# prototype1.net
KiCad netlist of a schematic drawn in EAGLE
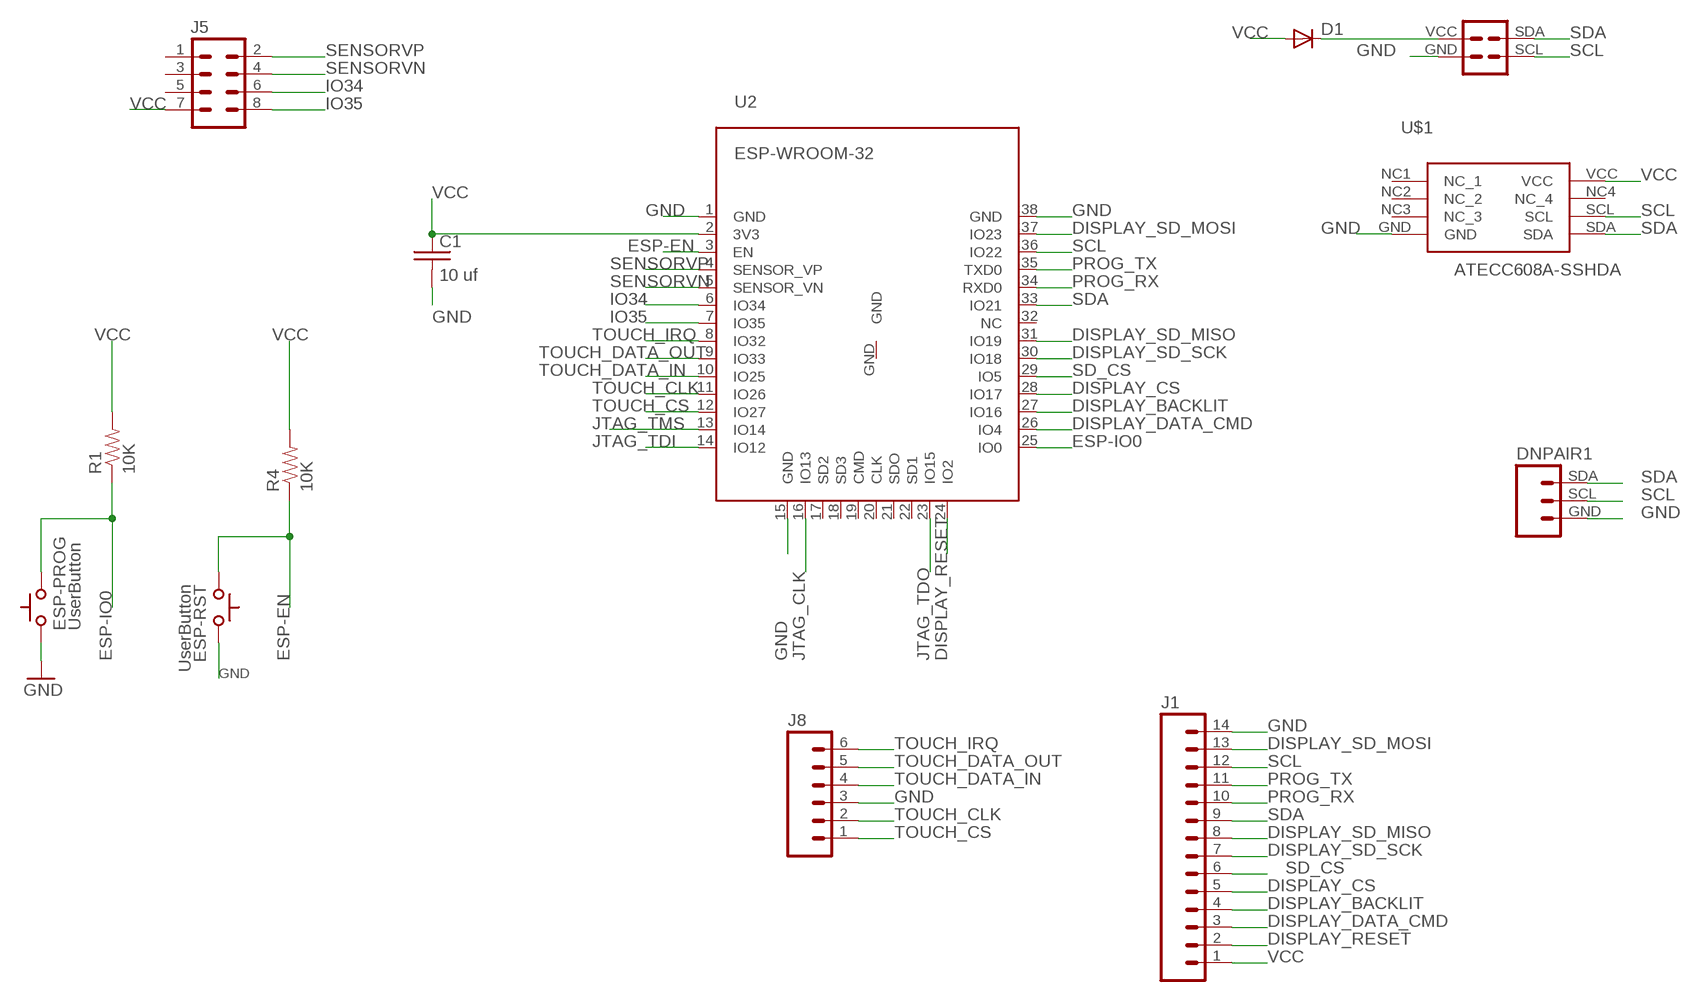
[diagram p0: schematic, sheet 1]
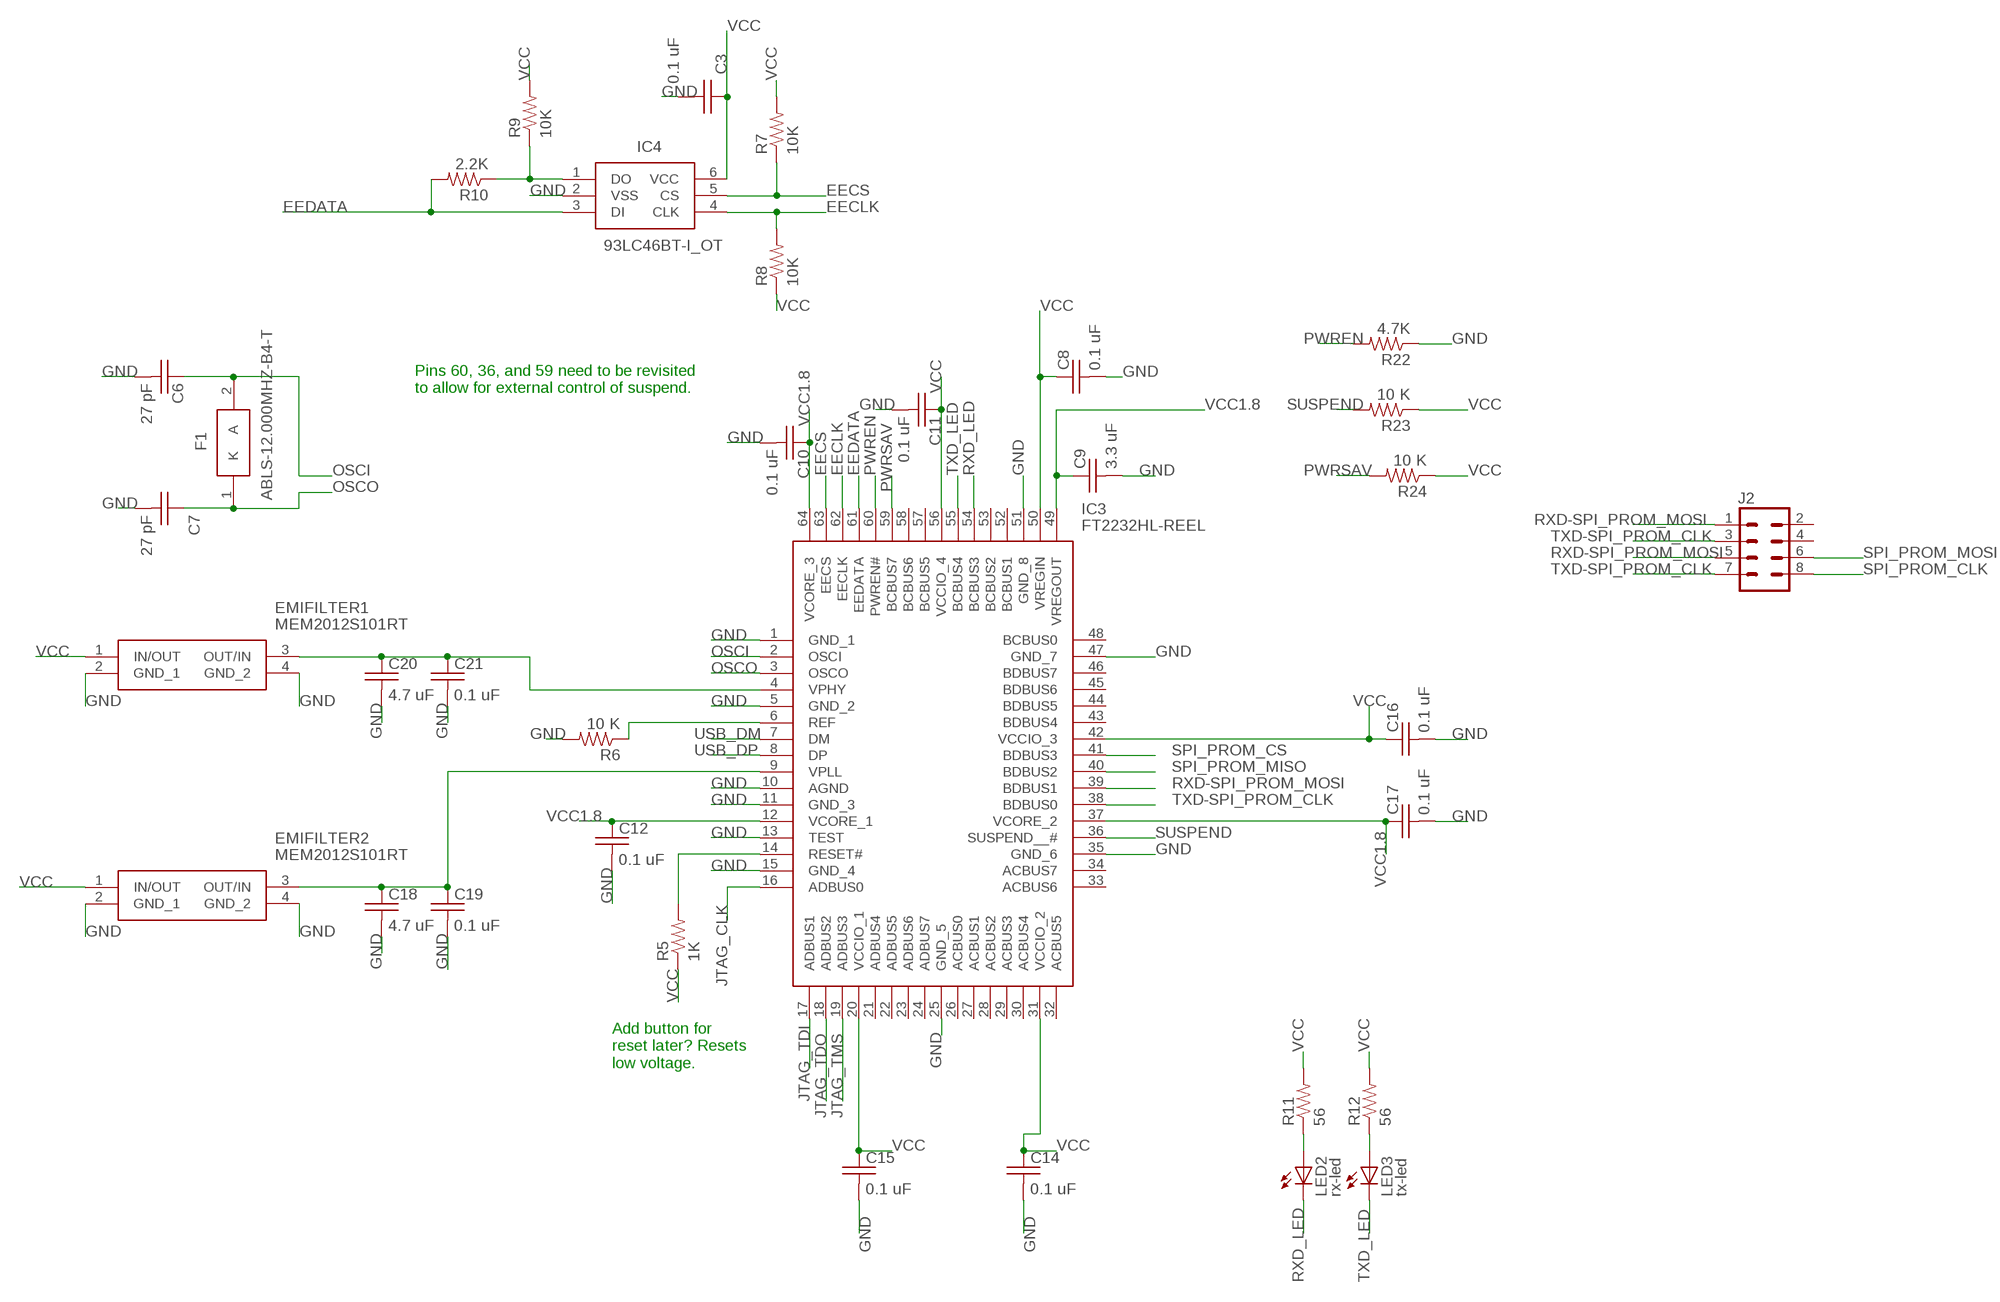
[diagram p1: schematic, sheet 2]
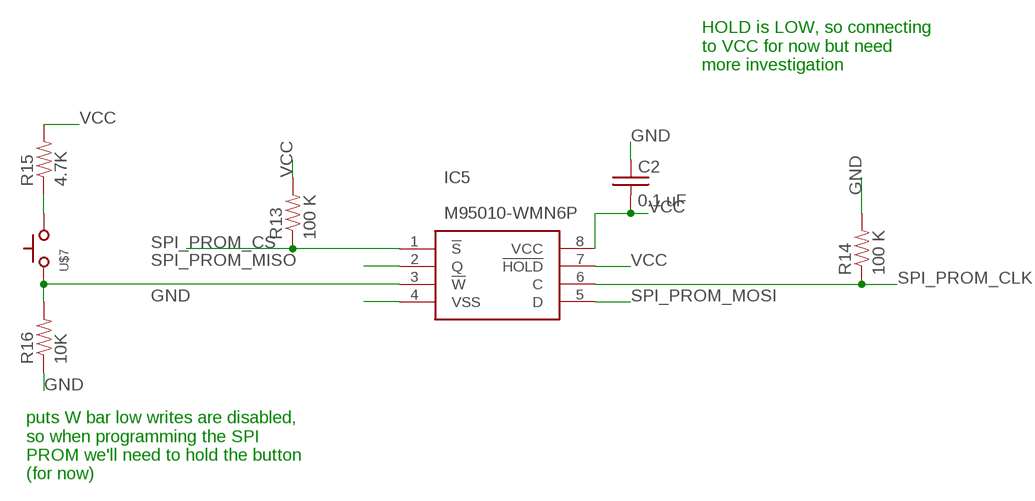
[diagram p2: schematic, sheet 3]
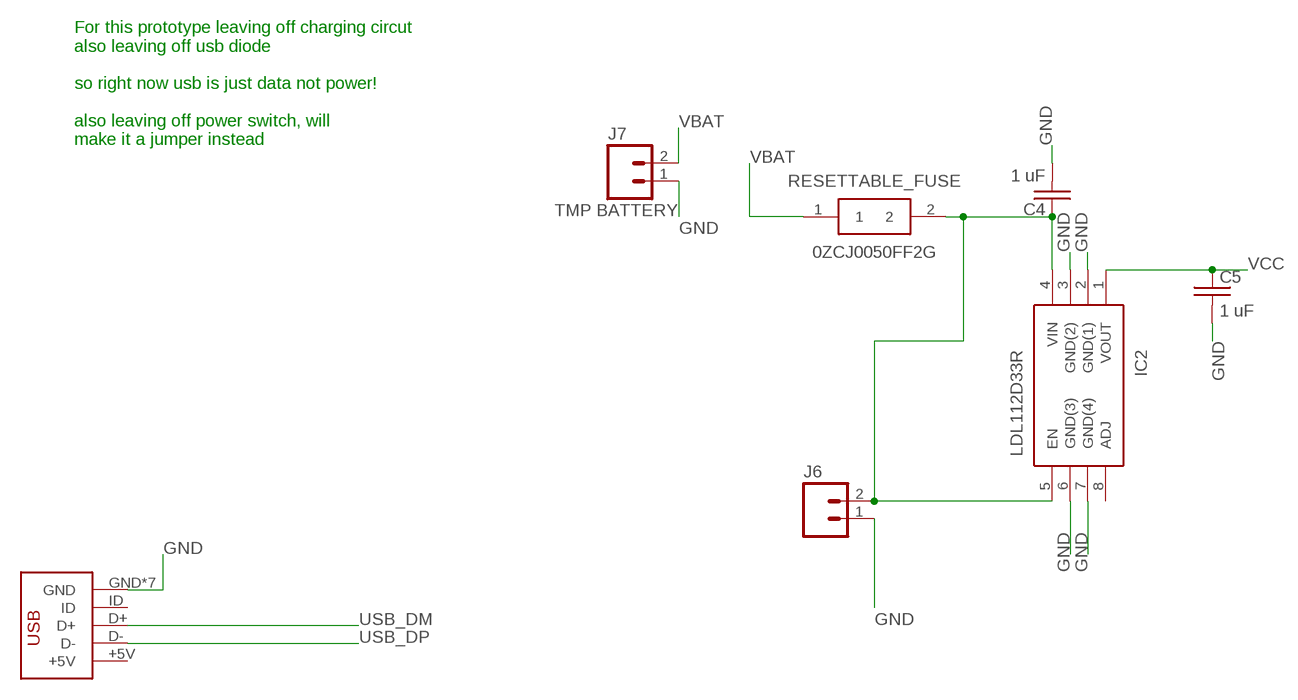
[diagram p3: schematic, sheet 4]
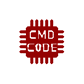
[diagram p4: schematic, sheet 5]

(export (version "E")
  (design (tool "Eeschema 10.0.6"))
  (components
    (comp (ref "C3")
      (value "0.1 uF")
      (footprint "eagle-import:C0805")
      (libsource (lib "eagle-import") (part "C-USC0805"))
    )
    (comp (ref "C6")
      (value "27 pF")
      (footprint "eagle-import:C0805")
      (libsource (lib "eagle-import") (part "C-USC0805"))
    )
    (comp (ref "C7")
      (value "27 pF")
      (footprint "eagle-import:C0805")
      (libsource (lib "eagle-import") (part "C-USC0805"))
    )
    (comp (ref "C8")
      (value "0.1 uF")
      (footprint "eagle-import:C0805")
      (libsource (lib "eagle-import") (part "C-USC0805"))
    )
    (comp (ref "C9")
      (value "3.3 uF")
      (footprint "eagle-import:C0805")
      (libsource (lib "eagle-import") (part "C-USC0805"))
    )
    (comp (ref "C10")
      (value "0.1 uF")
      (footprint "eagle-import:C0805")
      (libsource (lib "eagle-import") (part "C-USC0805"))
    )
    (comp (ref "C11")
      (value "0.1 uF")
      (footprint "eagle-import:C0805")
      (libsource (lib "eagle-import") (part "C-USC0805"))
    )
    (comp (ref "C12")
      (value "0.1 uF")
      (footprint "eagle-import:C0805")
      (libsource (lib "eagle-import") (part "C-USC0805"))
    )
    (comp (ref "C14")
      (value "0.1 uF")
      (footprint "eagle-import:C0805")
      (libsource (lib "eagle-import") (part "C-USC0805"))
    )
    (comp (ref "C15")
      (value "0.1 uF")
      (footprint "eagle-import:C0805")
      (libsource (lib "eagle-import") (part "C-USC0805"))
    )
    (comp (ref "C16")
      (value "0.1 uF")
      (footprint "eagle-import:C0805")
      (libsource (lib "eagle-import") (part "C-USC0805"))
    )
    (comp (ref "C17")
      (value "0.1 uF")
      (footprint "eagle-import:C0805")
      (libsource (lib "eagle-import") (part "C-USC0805"))
    )
    (comp (ref "C18")
      (value "4.7 uF")
      (footprint "eagle-import:C0805")
      (libsource (lib "eagle-import") (part "C-USC0805"))
    )
    (comp (ref "C19")
      (value "0.1 uF")
      (footprint "eagle-import:C0805")
      (libsource (lib "eagle-import") (part "C-USC0805"))
    )
    (comp (ref "C20")
      (value "4.7 uF")
      (footprint "eagle-import:C0805")
      (libsource (lib "eagle-import") (part "C-USC0805"))
    )
    (comp (ref "C21")
      (value "0.1 uF")
      (footprint "eagle-import:C0805")
      (libsource (lib "eagle-import") (part "C-USC0805"))
    )
    (comp (ref "EMIFILTER1")
      (value "MEM2012S101RT")
      (footprint "eagle-import:MEM2012S101RT")
      (libsource (lib "eagle-import") (part "MEM2012S101RT"))
    )
    (comp (ref "EMIFILTER2")
      (value "MEM2012S101RT")
      (footprint "eagle-import:MEM2012S101RT")
      (libsource (lib "eagle-import") (part "MEM2012S101RT"))
    )
    (comp (ref "F1")
      (value "ABLS-12.000MHZ-B4-T")
      (footprint "eagle-import:HC_49US-(AT49)_1")
      (fields
        (field (name "MOUSER_PART_NUMBER") "815-ABLS-12.0M-T")
        (field (name "RS_PART_NUMBER") "1710207")
      )
      (libsource (lib "eagle-import") (part "ABLS-12.000MHZ-B4-T"))
    )
    (comp (ref "IC3")
      (value "FT2232HL-REEL")
      (footprint "eagle-import:QFP50P1200X1200X160-64N")
      (fields (field (name "MOUSER_PART_NUMBER") "895-FT2232HL"))
      (libsource (lib "eagle-import") (part "FT2232HL-REEL"))
    )
    (comp (ref "IC4")
      (value "93LC46BT-I_OT")
      (footprint "eagle-import:SOT95P270X145-6N")
      (fields
        (field (name "MANUFACTURER_PART_NUMBER") "93LC46BT-I/OT")
        (field (name "MOUSER_PART_NUMBER") "579-93LC46BT-I/OT")
      )
      (libsource (lib "eagle-import") (part "93LC46BT-I_OT"))
    )
    (comp (ref "J2")
      (value "M04X2")
      (footprint "eagle-import:2X4")
      (libsource (lib "eagle-import") (part "M04X2"))
    )
    (comp (ref "LED2")
      (value "rx-led")
      (footprint "eagle-import:LED3MM")
      (libsource (lib "eagle-import") (part "LED3MM"))
    )
    (comp (ref "LED3")
      (value "tx-led")
      (footprint "eagle-import:LED3MM")
      (libsource (lib "eagle-import") (part "LED3MM"))
    )
    (comp (ref "R5")
      (value "1K")
      (footprint "eagle-import:0805")
      (libsource (lib "eagle-import") (part "passives_RESISTOR0805-RES"))
    )
    (comp (ref "R6")
      (value "10 K")
      (footprint "eagle-import:0805")
      (libsource (lib "eagle-import") (part "passives_RESISTOR0805-RES"))
    )
    (comp (ref "R7")
      (value "10K")
      (footprint "eagle-import:0805")
      (libsource (lib "eagle-import") (part "passives_RESISTOR0805-RES"))
    )
    (comp (ref "R8")
      (value "10K")
      (footprint "eagle-import:0805")
      (libsource (lib "eagle-import") (part "passives_RESISTOR0805-RES"))
    )
    (comp (ref "R9")
      (value "10K")
      (footprint "eagle-import:0805")
      (libsource (lib "eagle-import") (part "passives_RESISTOR0805-RES"))
    )
    (comp (ref "R10")
      (value "2.2K")
      (footprint "eagle-import:0805")
      (libsource (lib "eagle-import") (part "passives_RESISTOR0805-RES"))
    )
    (comp (ref "R11")
      (value "56")
      (footprint "eagle-import:0805")
      (libsource (lib "eagle-import") (part "passives_RESISTOR0805-RES"))
    )
    (comp (ref "R12")
      (value "56")
      (footprint "eagle-import:0805")
      (libsource (lib "eagle-import") (part "passives_RESISTOR0805-RES"))
    )
    (comp (ref "R22")
      (value "4.7K")
      (footprint "eagle-import:0805")
      (libsource (lib "eagle-import") (part "passives_RESISTOR0805-RES"))
    )
    (comp (ref "R23")
      (value "10 K")
      (footprint "eagle-import:0805")
      (libsource (lib "eagle-import") (part "passives_RESISTOR0805-RES"))
    )
    (comp (ref "R24")
      (value "10 K")
      (footprint "eagle-import:0805")
      (libsource (lib "eagle-import") (part "passives_RESISTOR0805-RES"))
    )
    (comp (ref "U$3")
      (value "CMD_C0DE_LOGOCMD_CODE_LOGO_TOP_COPPER")
      (footprint "eagle-import:CMD_C0DE_LOGO_TOP_COPPER")
      (libsource (lib "eagle-import") (part "CMD_C0DE_LOGOCMD_CODE_LOGO_TOP_COPPER"))
    )
    (comp (ref "C4")
      (value "1 uF")
      (footprint "eagle-import:C0805")
      (libsource (lib "eagle-import") (part "C-USC0805"))
    )
    (comp (ref "C5")
      (value "1 uF")
      (footprint "eagle-import:C0805")
      (libsource (lib "eagle-import") (part "C-USC0805"))
    )
    (comp (ref "IC2")
      (value "LDL112D33R")
      (footprint "eagle-import:SOIC127P600X175-8N")
      (libsource (lib "eagle-import") (part "LDL112D33R"))
    )
    (comp (ref "J6")
      (value "M02PTH")
      (footprint "eagle-import:1X02")
      (libsource (lib "eagle-import") (part "M02PTH"))
    )
    (comp (ref "J7")
      (value "TMP BATTERY")
      (footprint "eagle-import:1X02")
      (libsource (lib "eagle-import") (part "M02PTH"))
    )
    (comp (ref "RESETTABLE_FUSE")
      (value "0ZCJ0050FF2G")
      (footprint "eagle-import:FUSC3216X55N")
      (libsource (lib "eagle-import") (part "0ZCJ0050FF2G"))
    )
    (comp (ref "U$2")
      (value "DX4R005JJ2DX4R005JJ2")
      (footprint "eagle-import:DX4R005JJ2")
      (libsource (lib "eagle-import") (part "DX4R005JJ2DX4R005JJ2"))
    )
    (comp (ref "C2")
      (value "0.1 uF")
      (footprint "eagle-import:C0805")
      (libsource (lib "eagle-import") (part "C-USC0805"))
    )
    (comp (ref "IC5")
      (value "M95010-WMN6P")
      (footprint "eagle-import:SOIC127P600X175-8N")
      (fields
        (field (name "MOUSER_PART_NUMBER") "511-M95010-WMN6P")
        (field (name "RS_PART_NUMBER") "7147617")
      )
      (libsource (lib "eagle-import") (part "M95010-WMN6P"))
    )
    (comp (ref "R13")
      (value "100 K")
      (footprint "eagle-import:0805")
      (libsource (lib "eagle-import") (part "passives_RESISTOR0805-RES"))
    )
    (comp (ref "R14")
      (value "100 K")
      (footprint "eagle-import:0805")
      (libsource (lib "eagle-import") (part "passives_RESISTOR0805-RES"))
    )
    (comp (ref "R15")
      (value "4.7K")
      (footprint "eagle-import:0805")
      (libsource (lib "eagle-import") (part "passives_RESISTOR0805-RES"))
    )
    (comp (ref "R16")
      (value "10K")
      (footprint "eagle-import:0805")
      (libsource (lib "eagle-import") (part "passives_RESISTOR0805-RES"))
    )
    (comp (ref "U$7")
      (value "SWITCH_TACTILETACTILE-2PIN-NARROW")
      (footprint "eagle-import:TACTILE-2PIN-NARROW")
      (libsource (lib "eagle-import") (part "switches_SWITCH_TACTILETACTILE-2PIN-NARROW"))
    )
    (comp (ref "C1")
      (value "10 uf")
      (footprint "eagle-import:C0805")
      (libsource (lib "eagle-import") (part "C-USC0805"))
    )
    (comp (ref "D1")
      (value "DIODESMA")
      (footprint "eagle-import:SMA-DIODE")
      (libsource (lib "eagle-import") (part "DIODESMA"))
    )
    (comp (ref "DNPAIR1")
      (value "DARKNET_8_PAIR_CONNECTORPTH")
      (footprint "eagle-import:1X03")
      (libsource (lib "eagle-import") (part "DARKNET_8_PAIR_CONNECTORPTH"))
    )
    (comp (ref "ESP-PROG")
      (value "UserButton")
      (footprint "eagle-import:TACTILE-2PIN-NARROW")
      (libsource (lib "eagle-import") (part "SWITCH_TACTILETACTILE-2PIN-NARROW"))
    )
    (comp (ref "ESP-RST")
      (value "UserButton")
      (footprint "eagle-import:TACTILE-2PIN-NARROW")
      (libsource (lib "eagle-import") (part "SWITCH_TACTILETACTILE-2PIN-NARROW"))
    )
    (comp (ref "J1")
      (value "M14")
      (footprint "eagle-import:1X14")
      (libsource (lib "eagle-import") (part "M14"))
    )
    (comp (ref "J5")
      (value "M04X2")
      (footprint "eagle-import:2X4")
      (libsource (lib "eagle-import") (part "M04X2"))
    )
    (comp (ref "J8")
      (value "M06NO_SILK_YES_STOP")
      (footprint "eagle-import:1X06_NO_SILK_YES_STOP")
      (libsource (lib "eagle-import") (part "M06NO_SILK_YES_STOP"))
    )
    (comp (ref "R1")
      (value "10K")
      (footprint "eagle-import:0805")
      (libsource (lib "eagle-import") (part "RESISTOR0805-RES"))
    )
    (comp (ref "R4")
      (value "10K")
      (footprint "eagle-import:0805")
      (libsource (lib "eagle-import") (part "RESISTOR0805-RES"))
    )
    (comp (ref "SHITTY_ADDON")
      (value "SAO1")
      (footprint "eagle-import:DC26SHITTY_ADDON_CONNECTOR")
      (libsource (lib "eagle-import") (part "DC26_SHITTY_ADDON_CONNECTORPTH"))
    )
    (comp (ref "U$1")
      (value "ATECC608A-SSHDA")
      (footprint "eagle-import:8-SOIC")
      (libsource (lib "eagle-import") (part "ATECC608A-SSHDA"))
    )
    (comp (ref "U2")
      (value "ESP-WROOM-32")
      (footprint "eagle-import:ESP-WROOM-32")
      (libsource (lib "eagle-import") (part "ESP-WROOM-32"))
    )
  )
  (nets
    (net (code "1") (name "DISPLAY_BACKLIT") (class "Default")
      (node (ref "J1") (pin "4") (pinfunction "4_4") (pintype "passive"))
      (node (ref "U2") (pin "27") (pinfunction "IO16_27") (pintype "bidirectional"))
    )
    (net (code "2") (name "DISPLAY_CS") (class "Default")
      (node (ref "J1") (pin "5") (pinfunction "5_5") (pintype "passive"))
      (node (ref "U2") (pin "28") (pinfunction "IO17_28") (pintype "bidirectional"))
    )
    (net (code "3") (name "DISPLAY_DATA_CMD") (class "Default")
      (node (ref "J1") (pin "3") (pinfunction "3_3") (pintype "passive"))
      (node (ref "U2") (pin "26") (pinfunction "IO4_26") (pintype "bidirectional"))
    )
    (net (code "4") (name "DISPLAY_RESET") (class "Default")
      (node (ref "J1") (pin "2") (pinfunction "2_2") (pintype "passive"))
      (node (ref "U2") (pin "24") (pinfunction "IO2_24") (pintype "bidirectional"))
    )
    (net (code "5") (name "DISPLAY_SD_MISO") (class "Default")
      (node (ref "J1") (pin "8") (pinfunction "8_8") (pintype "passive"))
      (node (ref "U2") (pin "31") (pinfunction "IO19_31") (pintype "bidirectional"))
    )
    (net (code "6") (name "DISPLAY_SD_MOSI") (class "Default")
      (node (ref "J1") (pin "13") (pinfunction "13_13") (pintype "passive"))
      (node (ref "U2") (pin "37") (pinfunction "IO23_37") (pintype "bidirectional"))
    )
    (net (code "7") (name "DISPLAY_SD_SCK") (class "Default")
      (node (ref "J1") (pin "7") (pinfunction "7_7") (pintype "passive"))
      (node (ref "U2") (pin "30") (pinfunction "IO18_30") (pintype "bidirectional"))
    )
    (net (code "8") (name "EECLK") (class "Default")
      (node (ref "IC3") (pin "62") (pinfunction "EECLK_62") (pintype "bidirectional"))
      (node (ref "IC4") (pin "4") (pinfunction "CLK_4") (pintype "input"))
      (node (ref "R8") (pin "2") (pinfunction "2_2") (pintype "passive"))
    )
    (net (code "9") (name "EECS") (class "Default")
      (node (ref "IC3") (pin "63") (pinfunction "EECS_63") (pintype "bidirectional"))
      (node (ref "IC4") (pin "5") (pinfunction "CS_5") (pintype "input"))
      (node (ref "R7") (pin "1") (pinfunction "1_1") (pintype "passive"))
    )
    (net (code "10") (name "EEDATA") (class "Default")
      (node (ref "IC3") (pin "61") (pinfunction "EEDATA_61") (pintype "bidirectional"))
      (node (ref "IC4") (pin "3") (pinfunction "DI_3") (pintype "bidirectional"))
      (node (ref "R10") (pin "2") (pinfunction "2_2") (pintype "passive"))
    )
    (net (code "11") (name "ESP-EN") (class "Default")
      (node (ref "ESP-RST") (pin "P$2") (pinfunction "C_P$2") (pintype "passive"))
      (node (ref "R4") (pin "1") (pinfunction "1_1") (pintype "passive"))
      (node (ref "U2") (pin "3") (pinfunction "EN_3") (pintype "bidirectional"))
    )
    (net (code "12") (name "ESP-IO0") (class "Default")
      (node (ref "ESP-PROG") (pin "P$1") (pinfunction "A_P$1") (pintype "passive"))
      (node (ref "R1") (pin "1") (pinfunction "1_1") (pintype "passive"))
      (node (ref "U2") (pin "25") (pinfunction "IO0_25") (pintype "bidirectional"))
    )
    (net (code "13") (name "GND") (class "Default")
      (node (ref "C1") (pin "2") (pinfunction "2_2") (pintype "passive"))
      (node (ref "C10") (pin "2") (pinfunction "2_2") (pintype "passive"))
      (node (ref "C11") (pin "2") (pinfunction "2_2") (pintype "passive"))
      (node (ref "C12") (pin "2") (pinfunction "2_2") (pintype "passive"))
      (node (ref "C14") (pin "2") (pinfunction "2_2") (pintype "passive"))
      (node (ref "C15") (pin "2") (pinfunction "2_2") (pintype "passive"))
      (node (ref "C16") (pin "2") (pinfunction "2_2") (pintype "passive"))
      (node (ref "C17") (pin "2") (pinfunction "2_2") (pintype "passive"))
      (node (ref "C18") (pin "2") (pinfunction "2_2") (pintype "passive"))
      (node (ref "C19") (pin "2") (pinfunction "2_2") (pintype "passive"))
      (node (ref "C2") (pin "1") (pinfunction "1_1") (pintype "passive"))
      (node (ref "C20") (pin "2") (pinfunction "2_2") (pintype "passive"))
      (node (ref "C21") (pin "2") (pinfunction "2_2") (pintype "passive"))
      (node (ref "C3") (pin "2") (pinfunction "2_2") (pintype "passive"))
      (node (ref "C4") (pin "2") (pinfunction "2_2") (pintype "passive"))
      (node (ref "C5") (pin "2") (pinfunction "2_2") (pintype "passive"))
      (node (ref "C6") (pin "2") (pinfunction "2_2") (pintype "passive"))
      (node (ref "C7") (pin "2") (pinfunction "2_2") (pintype "passive"))
      (node (ref "C8") (pin "2") (pinfunction "2_2") (pintype "passive"))
      (node (ref "C9") (pin "2") (pinfunction "2_2") (pintype "passive"))
      (node (ref "DNPAIR1") (pin "GND") (pinfunction "GND_GND") (pintype "power_in"))
      (node (ref "EMIFILTER1") (pin "2") (pinfunction "GND_1_2") (pintype "bidirectional"))
      (node (ref "EMIFILTER1") (pin "4") (pinfunction "GND_2_4") (pintype "bidirectional"))
      (node (ref "EMIFILTER2") (pin "2") (pinfunction "GND_1_2") (pintype "bidirectional"))
      (node (ref "EMIFILTER2") (pin "4") (pinfunction "GND_2_4") (pintype "bidirectional"))
      (node (ref "ESP-PROG") (pin "P$2") (pinfunction "C_P$2") (pintype "passive"))
      (node (ref "ESP-RST") (pin "P$1") (pinfunction "A_P$1") (pintype "passive"))
      (node (ref "IC2") (pin "2") (pinfunction "GND(1)_2") (pintype "bidirectional"))
      (node (ref "IC2") (pin "3") (pinfunction "GND(2)_3") (pintype "bidirectional"))
      (node (ref "IC2") (pin "6") (pinfunction "GND(3)_6") (pintype "bidirectional"))
      (node (ref "IC2") (pin "7") (pinfunction "GND(4)_7") (pintype "bidirectional"))
      (node (ref "IC3") (pin "1") (pinfunction "GND_1_1") (pintype "bidirectional"))
      (node (ref "IC3") (pin "10") (pinfunction "AGND_10") (pintype "bidirectional"))
      (node (ref "IC3") (pin "11") (pinfunction "GND_3_11") (pintype "bidirectional"))
      (node (ref "IC3") (pin "13") (pinfunction "TEST_13") (pintype "bidirectional"))
      (node (ref "IC3") (pin "15") (pinfunction "GND_4_15") (pintype "bidirectional"))
      (node (ref "IC3") (pin "25") (pinfunction "GND_5_25") (pintype "bidirectional"))
      (node (ref "IC3") (pin "35") (pinfunction "GND_6_35") (pintype "bidirectional"))
      (node (ref "IC3") (pin "47") (pinfunction "GND_7_47") (pintype "bidirectional"))
      (node (ref "IC3") (pin "5") (pinfunction "GND_2_5") (pintype "bidirectional"))
      (node (ref "IC3") (pin "51") (pinfunction "GND_8_51") (pintype "bidirectional"))
      (node (ref "IC4") (pin "2") (pinfunction "VSS_2") (pintype "power_in"))
      (node (ref "IC5") (pin "4") (pinfunction "VSS_4") (pintype "power_in"))
      (node (ref "J1") (pin "14") (pinfunction "14_14") (pintype "passive"))
      (node (ref "J6") (pin "1") (pinfunction "1_1") (pintype "passive"))
      (node (ref "J7") (pin "1") (pinfunction "1_1") (pintype "passive"))
      (node (ref "J8") (pin "3") (pinfunction "3_3") (pintype "passive"))
      (node (ref "R14") (pin "2") (pinfunction "2_2") (pintype "passive"))
      (node (ref "R16") (pin "1") (pinfunction "1_1") (pintype "passive"))
      (node (ref "R22") (pin "1") (pinfunction "1_1") (pintype "passive"))
      (node (ref "R6") (pin "2") (pinfunction "2_2") (pintype "passive"))
      (node (ref "SHITTY_ADDON") (pin "GND") (pinfunction "GND_GND") (pintype "power_in"))
      (node (ref "U$1") (pin "GND") (pinfunction "GND_GND") (pintype "power_in"))
      (node (ref "U$2") (pin "GND") (pinfunction "GND_GND") (pintype "bidirectional"))
      (node (ref "U$2") (pin "P$10") (pinfunction "GND_P$10") (pintype "bidirectional"))
      (node (ref "U$2") (pin "P$11") (pinfunction "GND_P$11") (pintype "bidirectional"))
      (node (ref "U$2") (pin "P$6") (pinfunction "GND_P$6") (pintype "bidirectional"))
      (node (ref "U$2") (pin "P$7") (pinfunction "GND_P$7") (pintype "bidirectional"))
      (node (ref "U$2") (pin "P$8") (pinfunction "GND_P$8") (pintype "bidirectional"))
      (node (ref "U$2") (pin "P$9") (pinfunction "GND_P$9") (pintype "bidirectional"))
      (node (ref "U2") (pin "1") (pinfunction "GND_1") (pintype "bidirectional"))
      (node (ref "U2") (pin "15") (pinfunction "GND_15") (pintype "bidirectional"))
      (node (ref "U2") (pin "38") (pinfunction "GND_38") (pintype "bidirectional"))
    )
    (net (code "14") (name "IO34") (class "Default")
      (node (ref "J5") (pin "6") (pinfunction "6_6") (pintype "passive"))
      (node (ref "U2") (pin "6") (pinfunction "IO34_6") (pintype "bidirectional"))
    )
    (net (code "15") (name "IO35") (class "Default")
      (node (ref "J5") (pin "8") (pinfunction "8_8") (pintype "passive"))
      (node (ref "U2") (pin "7") (pinfunction "IO35_7") (pintype "bidirectional"))
    )
    (net (code "16") (name "JTAG_CLK") (class "Default")
      (node (ref "IC3") (pin "16") (pinfunction "ADBUS0_16") (pintype "bidirectional"))
      (node (ref "U2") (pin "16") (pinfunction "IO13_16") (pintype "bidirectional"))
    )
    (net (code "17") (name "JTAG_TDI") (class "Default")
      (node (ref "IC3") (pin "17") (pinfunction "ADBUS1_17") (pintype "bidirectional"))
      (node (ref "U2") (pin "14") (pinfunction "IO12_14") (pintype "bidirectional"))
    )
    (net (code "18") (name "JTAG_TDO") (class "Default")
      (node (ref "IC3") (pin "18") (pinfunction "ADBUS2_18") (pintype "bidirectional"))
      (node (ref "U2") (pin "23") (pinfunction "IO15_23") (pintype "bidirectional"))
    )
    (net (code "19") (name "JTAG_TMS") (class "Default")
      (node (ref "IC3") (pin "19") (pinfunction "ADBUS3_19") (pintype "bidirectional"))
      (node (ref "U2") (pin "13") (pinfunction "IO14_13") (pintype "bidirectional"))
    )
    (net (code "20") (name "Net-(D1-PadC)") (class "Default")
      (node (ref "D1") (pin "C") (pinfunction "C_C") (pintype "passive"))
      (node (ref "SHITTY_ADDON") (pin "VCC") (pinfunction "VCC_VCC") (pintype "power_in"))
    )
    (net (code "21") (name "Net-(EMIFILTER1-OUT{slash}IN)") (class "Default")
      (node (ref "C20") (pin "1") (pinfunction "1_1") (pintype "passive"))
      (node (ref "C21") (pin "1") (pinfunction "1_1") (pintype "passive"))
      (node (ref "EMIFILTER1") (pin "3") (pinfunction "OUT/IN_3") (pintype "bidirectional"))
      (node (ref "IC3") (pin "4") (pinfunction "VPHY_4") (pintype "bidirectional"))
    )
    (net (code "22") (name "Net-(EMIFILTER2-OUT{slash}IN)") (class "Default")
      (node (ref "C18") (pin "1") (pinfunction "1_1") (pintype "passive"))
      (node (ref "C19") (pin "1") (pinfunction "1_1") (pintype "passive"))
      (node (ref "EMIFILTER2") (pin "3") (pinfunction "OUT/IN_3") (pintype "bidirectional"))
      (node (ref "IC3") (pin "9") (pinfunction "VPLL_9") (pintype "bidirectional"))
    )
    (net (code "23") (name "Net-(IC2-EN)") (class "Default")
      (node (ref "C4") (pin "1") (pinfunction "1_1") (pintype "passive"))
      (node (ref "IC2") (pin "4") (pinfunction "VIN_4") (pintype "bidirectional"))
      (node (ref "IC2") (pin "5") (pinfunction "EN_5") (pintype "bidirectional"))
      (node (ref "J6") (pin "2") (pinfunction "2_2") (pintype "passive"))
      (node (ref "RESETTABLE_FUSE") (pin "2") (pinfunction "2_2") (pintype "passive"))
    )
    (net (code "24") (name "Net-(IC3-REF)") (class "Default")
      (node (ref "IC3") (pin "6") (pinfunction "REF_6") (pintype "bidirectional"))
      (node (ref "R6") (pin "1") (pinfunction "1_1") (pintype "passive"))
    )
    (net (code "25") (name "Net-(IC3-RESET#)") (class "Default")
      (node (ref "IC3") (pin "14") (pinfunction "RESET#_14") (pintype "bidirectional"))
      (node (ref "R5") (pin "2") (pinfunction "2_2") (pintype "passive"))
    )
    (net (code "26") (name "Net-(IC4-DO)") (class "Default")
      (node (ref "IC4") (pin "1") (pinfunction "DO_1") (pintype "bidirectional"))
      (node (ref "R10") (pin "1") (pinfunction "1_1") (pintype "passive"))
      (node (ref "R9") (pin "1") (pinfunction "1_1") (pintype "passive"))
    )
    (net (code "27") (name "Net-(IC5-~{W})") (class "Default")
      (node (ref "IC5") (pin "3") (pinfunction "~{W}_3") (pintype "bidirectional"))
      (node (ref "R16") (pin "2") (pinfunction "2_2") (pintype "passive"))
      (node (ref "U$7") (pin "P$2") (pinfunction "C_P$2") (pintype "passive"))
    )
    (net (code "28") (name "Net-(LED2-PadA)") (class "Default")
      (node (ref "LED2") (pin "A") (pinfunction "A_A") (pintype "input"))
      (node (ref "R11") (pin "1") (pinfunction "1_1") (pintype "passive"))
    )
    (net (code "29") (name "Net-(LED3-PadA)") (class "Default")
      (node (ref "LED3") (pin "A") (pinfunction "A_A") (pintype "input"))
      (node (ref "R12") (pin "1") (pinfunction "1_1") (pintype "passive"))
    )
    (net (code "30") (name "Net-(U$7-A)") (class "Default")
      (node (ref "R15") (pin "1") (pinfunction "1_1") (pintype "passive"))
      (node (ref "U$7") (pin "P$1") (pinfunction "A_P$1") (pintype "passive"))
    )
    (net (code "31") (name "OSCI") (class "Default")
      (node (ref "C6") (pin "1") (pinfunction "1_1") (pintype "passive"))
      (node (ref "F1") (pin "2") (pinfunction "A_2") (pintype "bidirectional"))
      (node (ref "IC3") (pin "2") (pinfunction "OSCI_2") (pintype "bidirectional"))
    )
    (net (code "32") (name "OSCO") (class "Default")
      (node (ref "C7") (pin "1") (pinfunction "1_1") (pintype "passive"))
      (node (ref "F1") (pin "1") (pinfunction "K_1") (pintype "bidirectional"))
      (node (ref "IC3") (pin "3") (pinfunction "OSCO_3") (pintype "bidirectional"))
    )
    (net (code "33") (name "PROG_RX") (class "Default")
      (node (ref "J1") (pin "10") (pinfunction "10_10") (pintype "passive"))
      (node (ref "U2") (pin "34") (pinfunction "RXD0_34") (pintype "bidirectional"))
    )
    (net (code "34") (name "PROG_TX") (class "Default")
      (node (ref "J1") (pin "11") (pinfunction "11_11") (pintype "passive"))
      (node (ref "U2") (pin "35") (pinfunction "TXD0_35") (pintype "bidirectional"))
    )
    (net (code "35") (name "PWREN") (class "Default")
      (node (ref "IC3") (pin "60") (pinfunction "PWREN#_60") (pintype "bidirectional"))
      (node (ref "R22") (pin "2") (pinfunction "2_2") (pintype "passive"))
    )
    (net (code "36") (name "PWRSAV") (class "Default")
      (node (ref "IC3") (pin "59") (pinfunction "BCBUS7_59") (pintype "bidirectional"))
      (node (ref "R24") (pin "2") (pinfunction "2_2") (pintype "passive"))
    )
    (net (code "37") (name "RXD-SPI_PROM_MOSI") (class "Default")
      (node (ref "IC3") (pin "39") (pinfunction "BDBUS1_39") (pintype "bidirectional"))
      (node (ref "J2") (pin "1") (pinfunction "1_1") (pintype "passive"))
      (node (ref "J2") (pin "5") (pinfunction "5_5") (pintype "passive"))
    )
    (net (code "38") (name "RXD_LED") (class "Default")
      (node (ref "IC3") (pin "54") (pinfunction "BCBUS3_54") (pintype "bidirectional"))
      (node (ref "LED2") (pin "K") (pinfunction "C_K") (pintype "output"))
    )
    (net (code "39") (name "SCL") (class "Default")
      (node (ref "DNPAIR1") (pin "SCL") (pinfunction "SCL_SCL") (pintype "bidirectional"))
      (node (ref "J1") (pin "12") (pinfunction "12_12") (pintype "passive"))
      (node (ref "SHITTY_ADDON") (pin "SCL") (pinfunction "SCL_SCL") (pintype "bidirectional"))
      (node (ref "U$1") (pin "SCL") (pinfunction "SCL_SCL") (pintype "bidirectional"))
      (node (ref "U2") (pin "36") (pinfunction "IO22_36") (pintype "bidirectional"))
    )
    (net (code "40") (name "SDA") (class "Default")
      (node (ref "DNPAIR1") (pin "SDA") (pinfunction "SDA_SDA") (pintype "bidirectional"))
      (node (ref "J1") (pin "9") (pinfunction "9_9") (pintype "passive"))
      (node (ref "SHITTY_ADDON") (pin "SDA") (pinfunction "SDA_SDA") (pintype "bidirectional"))
      (node (ref "U$1") (pin "SDA") (pinfunction "SDA_SDA") (pintype "bidirectional"))
      (node (ref "U2") (pin "33") (pinfunction "IO21_33") (pintype "bidirectional"))
    )
    (net (code "41") (name "SD_CS") (class "Default")
      (node (ref "J1") (pin "6") (pinfunction "6_6") (pintype "passive"))
      (node (ref "U2") (pin "29") (pinfunction "IO5_29") (pintype "bidirectional"))
    )
    (net (code "42") (name "SENSORVN") (class "Default")
      (node (ref "J5") (pin "4") (pinfunction "4_4") (pintype "passive"))
      (node (ref "U2") (pin "5") (pinfunction "SENSOR_VN_5") (pintype "bidirectional"))
    )
    (net (code "43") (name "SENSORVP") (class "Default")
      (node (ref "J5") (pin "2") (pinfunction "2_2") (pintype "passive"))
      (node (ref "U2") (pin "4") (pinfunction "SENSOR_VP_4") (pintype "bidirectional"))
    )
    (net (code "44") (name "SPI_PROM_CLK") (class "Default")
      (node (ref "IC5") (pin "6") (pinfunction "C_6") (pintype "bidirectional"))
      (node (ref "J2") (pin "8") (pinfunction "8_8") (pintype "passive"))
      (node (ref "R14") (pin "1") (pinfunction "1_1") (pintype "passive"))
    )
    (net (code "45") (name "SPI_PROM_CS") (class "Default")
      (node (ref "IC3") (pin "41") (pinfunction "BDBUS3_41") (pintype "bidirectional"))
      (node (ref "IC5") (pin "1") (pinfunction "~{S}_1") (pintype "bidirectional"))
      (node (ref "R13") (pin "1") (pinfunction "1_1") (pintype "passive"))
    )
    (net (code "46") (name "SPI_PROM_MISO") (class "Default")
      (node (ref "IC3") (pin "40") (pinfunction "BDBUS2_40") (pintype "bidirectional"))
      (node (ref "IC5") (pin "2") (pinfunction "Q_2") (pintype "output"))
    )
    (net (code "47") (name "SPI_PROM_MOSI") (class "Default")
      (node (ref "IC5") (pin "5") (pinfunction "D_5") (pintype "input"))
      (node (ref "J2") (pin "6") (pinfunction "6_6") (pintype "passive"))
    )
    (net (code "48") (name "SUSPEND") (class "Default")
      (node (ref "IC3") (pin "36") (pinfunction "SUSPEND__#_36") (pintype "bidirectional"))
      (node (ref "R23") (pin "2") (pinfunction "2_2") (pintype "passive"))
    )
    (net (code "49") (name "TOUCH_CLK") (class "Default")
      (node (ref "J8") (pin "2") (pinfunction "2_2") (pintype "passive"))
      (node (ref "U2") (pin "11") (pinfunction "IO26_11") (pintype "bidirectional"))
    )
    (net (code "50") (name "TOUCH_CS") (class "Default")
      (node (ref "J8") (pin "1") (pinfunction "1_1") (pintype "passive"))
      (node (ref "U2") (pin "12") (pinfunction "IO27_12") (pintype "bidirectional"))
    )
    (net (code "51") (name "TOUCH_DATA_IN") (class "Default")
      (node (ref "J8") (pin "4") (pinfunction "4_4") (pintype "passive"))
      (node (ref "U2") (pin "10") (pinfunction "IO25_10") (pintype "bidirectional"))
    )
    (net (code "52") (name "TOUCH_DATA_OUT") (class "Default")
      (node (ref "J8") (pin "5") (pinfunction "5_5") (pintype "passive"))
      (node (ref "U2") (pin "9") (pinfunction "IO33_9") (pintype "bidirectional"))
    )
    (net (code "53") (name "TOUCH_IRQ") (class "Default")
      (node (ref "J8") (pin "6") (pinfunction "6_6") (pintype "passive"))
      (node (ref "U2") (pin "8") (pinfunction "IO32_8") (pintype "bidirectional"))
    )
    (net (code "54") (name "TXD-SPI_PROM_CLK") (class "Default")
      (node (ref "IC3") (pin "38") (pinfunction "BDBUS0_38") (pintype "bidirectional"))
      (node (ref "J2") (pin "3") (pinfunction "3_3") (pintype "passive"))
      (node (ref "J2") (pin "7") (pinfunction "7_7") (pintype "passive"))
    )
    (net (code "55") (name "TXD_LED") (class "Default")
      (node (ref "IC3") (pin "55") (pinfunction "BCBUS4_55") (pintype "bidirectional"))
      (node (ref "LED3") (pin "K") (pinfunction "C_K") (pintype "output"))
    )
    (net (code "56") (name "USB_DM") (class "Default")
      (node (ref "IC3") (pin "7") (pinfunction "DM_7") (pintype "bidirectional"))
      (node (ref "U$2") (pin "D+") (pinfunction "D+_D+") (pintype "bidirectional"))
    )
    (net (code "57") (name "USB_DP") (class "Default")
      (node (ref "IC3") (pin "8") (pinfunction "DP_8") (pintype "bidirectional"))
      (node (ref "U$2") (pin "D-") (pinfunction "D-_D-") (pintype "bidirectional"))
    )
    (net (code "58") (name "VBAT") (class "Default")
      (node (ref "J7") (pin "2") (pinfunction "2_2") (pintype "passive"))
      (node (ref "RESETTABLE_FUSE") (pin "1") (pinfunction "1_1") (pintype "passive"))
    )
    (net (code "59") (name "VCC") (class "Default")
      (node (ref "C1") (pin "1") (pinfunction "1_1") (pintype "passive"))
      (node (ref "C11") (pin "1") (pinfunction "1_1") (pintype "passive"))
      (node (ref "C14") (pin "1") (pinfunction "1_1") (pintype "passive"))
      (node (ref "C15") (pin "1") (pinfunction "1_1") (pintype "passive"))
      (node (ref "C16") (pin "1") (pinfunction "1_1") (pintype "passive"))
      (node (ref "C2") (pin "2") (pinfunction "2_2") (pintype "passive"))
      (node (ref "C3") (pin "1") (pinfunction "1_1") (pintype "passive"))
      (node (ref "C5") (pin "1") (pinfunction "1_1") (pintype "passive"))
      (node (ref "C8") (pin "1") (pinfunction "1_1") (pintype "passive"))
      (node (ref "D1") (pin "A") (pinfunction "A_A") (pintype "passive"))
      (node (ref "EMIFILTER1") (pin "1") (pinfunction "IN/OUT_1") (pintype "bidirectional"))
      (node (ref "EMIFILTER2") (pin "1") (pinfunction "IN/OUT_1") (pintype "bidirectional"))
      (node (ref "IC2") (pin "1") (pinfunction "VOUT_1") (pintype "bidirectional"))
      (node (ref "IC3") (pin "20") (pinfunction "VCCIO_1_20") (pintype "bidirectional"))
      (node (ref "IC3") (pin "31") (pinfunction "VCCIO_2_31") (pintype "bidirectional"))
      (node (ref "IC3") (pin "42") (pinfunction "VCCIO_3_42") (pintype "bidirectional"))
      (node (ref "IC3") (pin "50") (pinfunction "VREGIN_50") (pintype "bidirectional"))
      (node (ref "IC3") (pin "56") (pinfunction "VCCIO_4_56") (pintype "bidirectional"))
      (node (ref "IC4") (pin "6") (pinfunction "VCC_6") (pintype "power_in"))
      (node (ref "IC5") (pin "7") (pinfunction "~{HOLD}_7") (pintype "bidirectional"))
      (node (ref "IC5") (pin "8") (pinfunction "VCC_8") (pintype "power_in"))
      (node (ref "J1") (pin "1") (pinfunction "1_1") (pintype "passive"))
      (node (ref "J5") (pin "7") (pinfunction "7_7") (pintype "passive"))
      (node (ref "R1") (pin "2") (pinfunction "2_2") (pintype "passive"))
      (node (ref "R11") (pin "2") (pinfunction "2_2") (pintype "passive"))
      (node (ref "R12") (pin "2") (pinfunction "2_2") (pintype "passive"))
      (node (ref "R13") (pin "2") (pinfunction "2_2") (pintype "passive"))
      (node (ref "R15") (pin "2") (pinfunction "2_2") (pintype "passive"))
      (node (ref "R23") (pin "1") (pinfunction "1_1") (pintype "passive"))
      (node (ref "R24") (pin "1") (pinfunction "1_1") (pintype "passive"))
      (node (ref "R4") (pin "2") (pinfunction "2_2") (pintype "passive"))
      (node (ref "R5") (pin "1") (pinfunction "1_1") (pintype "passive"))
      (node (ref "R7") (pin "2") (pinfunction "2_2") (pintype "passive"))
      (node (ref "R8") (pin "1") (pinfunction "1_1") (pintype "passive"))
      (node (ref "R9") (pin "2") (pinfunction "2_2") (pintype "passive"))
      (node (ref "U$1") (pin "VCC") (pinfunction "VCC_VCC") (pintype "power_in"))
      (node (ref "U2") (pin "2") (pinfunction "3V3_2") (pintype "bidirectional"))
    )
    (net (code "60") (name "VCC1.8") (class "Default")
      (node (ref "C10") (pin "1") (pinfunction "1_1") (pintype "passive"))
      (node (ref "C12") (pin "1") (pinfunction "1_1") (pintype "passive"))
      (node (ref "C17") (pin "1") (pinfunction "1_1") (pintype "passive"))
      (node (ref "C9") (pin "1") (pinfunction "1_1") (pintype "passive"))
      (node (ref "IC3") (pin "12") (pinfunction "VCORE_1_12") (pintype "bidirectional"))
      (node (ref "IC3") (pin "37") (pinfunction "VCORE_2_37") (pintype "bidirectional"))
      (node (ref "IC3") (pin "49") (pinfunction "VREGOUT_49") (pintype "bidirectional"))
      (node (ref "IC3") (pin "64") (pinfunction "VCORE_3_64") (pintype "bidirectional"))
    )
    (net (code "61") (name "unconnected-(IC2-ADJ-Pad8)") (class "Default")
      (node (ref "IC2") (pin "8") (pinfunction "ADJ_8") (pintype "bidirectional"))
    )
    (net (code "62") (name "unconnected-(IC3-ACBUS0-Pad26)") (class "Default")
      (node (ref "IC3") (pin "26") (pinfunction "ACBUS0_26") (pintype "bidirectional"))
    )
    (net (code "63") (name "unconnected-(IC3-ACBUS1-Pad27)") (class "Default")
      (node (ref "IC3") (pin "27") (pinfunction "ACBUS1_27") (pintype "bidirectional"))
    )
    (net (code "64") (name "unconnected-(IC3-ACBUS2-Pad28)") (class "Default")
      (node (ref "IC3") (pin "28") (pinfunction "ACBUS2_28") (pintype "bidirectional"))
    )
    (net (code "65") (name "unconnected-(IC3-ACBUS3-Pad29)") (class "Default")
      (node (ref "IC3") (pin "29") (pinfunction "ACBUS3_29") (pintype "bidirectional"))
    )
    (net (code "66") (name "unconnected-(IC3-ACBUS4-Pad30)") (class "Default")
      (node (ref "IC3") (pin "30") (pinfunction "ACBUS4_30") (pintype "bidirectional"))
    )
    (net (code "67") (name "unconnected-(IC3-ACBUS5-Pad32)") (class "Default")
      (node (ref "IC3") (pin "32") (pinfunction "ACBUS5_32") (pintype "bidirectional"))
    )
    (net (code "68") (name "unconnected-(IC3-ACBUS6-Pad33)") (class "Default")
      (node (ref "IC3") (pin "33") (pinfunction "ACBUS6_33") (pintype "bidirectional"))
    )
    (net (code "69") (name "unconnected-(IC3-ACBUS7-Pad34)") (class "Default")
      (node (ref "IC3") (pin "34") (pinfunction "ACBUS7_34") (pintype "bidirectional"))
    )
    (net (code "70") (name "unconnected-(IC3-ADBUS4-Pad21)") (class "Default")
      (node (ref "IC3") (pin "21") (pinfunction "ADBUS4_21") (pintype "bidirectional"))
    )
    (net (code "71") (name "unconnected-(IC3-ADBUS5-Pad22)") (class "Default")
      (node (ref "IC3") (pin "22") (pinfunction "ADBUS5_22") (pintype "bidirectional"))
    )
    (net (code "72") (name "unconnected-(IC3-ADBUS6-Pad23)") (class "Default")
      (node (ref "IC3") (pin "23") (pinfunction "ADBUS6_23") (pintype "bidirectional"))
    )
    (net (code "73") (name "unconnected-(IC3-ADBUS7-Pad24)") (class "Default")
      (node (ref "IC3") (pin "24") (pinfunction "ADBUS7_24") (pintype "bidirectional"))
    )
    (net (code "74") (name "unconnected-(IC3-BCBUS0-Pad48)") (class "Default")
      (node (ref "IC3") (pin "48") (pinfunction "BCBUS0_48") (pintype "bidirectional"))
    )
    (net (code "75") (name "unconnected-(IC3-BCBUS1-Pad52)") (class "Default")
      (node (ref "IC3") (pin "52") (pinfunction "BCBUS1_52") (pintype "bidirectional"))
    )
    (net (code "76") (name "unconnected-(IC3-BCBUS2-Pad53)") (class "Default")
      (node (ref "IC3") (pin "53") (pinfunction "BCBUS2_53") (pintype "bidirectional"))
    )
    (net (code "77") (name "unconnected-(IC3-BCBUS5-Pad57)") (class "Default")
      (node (ref "IC3") (pin "57") (pinfunction "BCBUS5_57") (pintype "bidirectional"))
    )
    (net (code "78") (name "unconnected-(IC3-BCBUS6-Pad58)") (class "Default")
      (node (ref "IC3") (pin "58") (pinfunction "BCBUS6_58") (pintype "bidirectional"))
    )
    (net (code "79") (name "unconnected-(IC3-BDBUS4-Pad43)") (class "Default")
      (node (ref "IC3") (pin "43") (pinfunction "BDBUS4_43") (pintype "bidirectional"))
    )
    (net (code "80") (name "unconnected-(IC3-BDBUS5-Pad44)") (class "Default")
      (node (ref "IC3") (pin "44") (pinfunction "BDBUS5_44") (pintype "bidirectional"))
    )
    (net (code "81") (name "unconnected-(IC3-BDBUS6-Pad45)") (class "Default")
      (node (ref "IC3") (pin "45") (pinfunction "BDBUS6_45") (pintype "bidirectional"))
    )
    (net (code "82") (name "unconnected-(IC3-BDBUS7-Pad46)") (class "Default")
      (node (ref "IC3") (pin "46") (pinfunction "BDBUS7_46") (pintype "bidirectional"))
    )
    (net (code "83") (name "unconnected-(J2-Pad2)") (class "Default")
      (node (ref "J2") (pin "2") (pinfunction "2_2") (pintype "passive"))
    )
    (net (code "84") (name "unconnected-(J2-Pad4)") (class "Default")
      (node (ref "J2") (pin "4") (pinfunction "4_4") (pintype "passive"))
    )
    (net (code "85") (name "unconnected-(J5-Pad1)") (class "Default")
      (node (ref "J5") (pin "1") (pinfunction "1_1") (pintype "passive"))
    )
    (net (code "86") (name "unconnected-(J5-Pad3)") (class "Default")
      (node (ref "J5") (pin "3") (pinfunction "3_3") (pintype "passive"))
    )
    (net (code "87") (name "unconnected-(J5-Pad5)") (class "Default")
      (node (ref "J5") (pin "5") (pinfunction "5_5") (pintype "passive"))
    )
    (net (code "88") (name "unconnected-(U$1-NC_1-PadNC1)") (class "Default")
      (node (ref "U$1") (pin "NC1") (pinfunction "NC_1_NC1") (pintype "no_connect"))
    )
    (net (code "89") (name "unconnected-(U$1-NC_2-PadNC2)") (class "Default")
      (node (ref "U$1") (pin "NC2") (pinfunction "NC_2_NC2") (pintype "no_connect"))
    )
    (net (code "90") (name "unconnected-(U$1-NC_3-PadNC3)") (class "Default")
      (node (ref "U$1") (pin "NC3") (pinfunction "NC_3_NC3") (pintype "no_connect"))
    )
    (net (code "91") (name "unconnected-(U$1-NC_4-PadNC4)") (class "Default")
      (node (ref "U$1") (pin "NC4") (pinfunction "NC_4_NC4") (pintype "no_connect"))
    )
    (net (code "92") (name "unconnected-(U$2-Pad+5V)") (class "Default")
      (node (ref "U$2") (pin "+5V") (pinfunction "+5V_+5V") (pintype "bidirectional"))
    )
    (net (code "93") (name "unconnected-(U$2-PadID)") (class "Default")
      (node (ref "U$2") (pin "ID") (pinfunction "ID_ID") (pintype "bidirectional"))
    )
    (net (code "94") (name "unconnected-(U2-CLK-Pad20)") (class "Default")
      (node (ref "U2") (pin "20") (pinfunction "CLK_20") (pintype "bidirectional"))
    )
    (net (code "95") (name "unconnected-(U2-CMD-Pad19)") (class "Default")
      (node (ref "U2") (pin "19") (pinfunction "CMD_19") (pintype "bidirectional"))
    )
    (net (code "96") (name "unconnected-(U2-NC-Pad32)") (class "Default")
      (node (ref "U2") (pin "32") (pinfunction "NC_32") (pintype "bidirectional"))
    )
    (net (code "97") (name "unconnected-(U2-PadGND)") (class "Default")
      (node (ref "U2") (pin "GND") (pinfunction "GND_GND") (pintype "bidirectional"))
    )
    (net (code "98") (name "unconnected-(U2-SD1-Pad22)") (class "Default")
      (node (ref "U2") (pin "22") (pinfunction "SD1_22") (pintype "bidirectional"))
    )
    (net (code "99") (name "unconnected-(U2-SD2-Pad17)") (class "Default")
      (node (ref "U2") (pin "17") (pinfunction "SD2_17") (pintype "bidirectional"))
    )
    (net (code "100") (name "unconnected-(U2-SD3-Pad18)") (class "Default")
      (node (ref "U2") (pin "18") (pinfunction "SD3_18") (pintype "bidirectional"))
    )
    (net (code "101") (name "unconnected-(U2-SDO-Pad21)") (class "Default")
      (node (ref "U2") (pin "21") (pinfunction "SDO_21") (pintype "bidirectional"))
    )
  )
)
